# ul-12.net
KiCad netlist of a schematic drawn in EAGLE
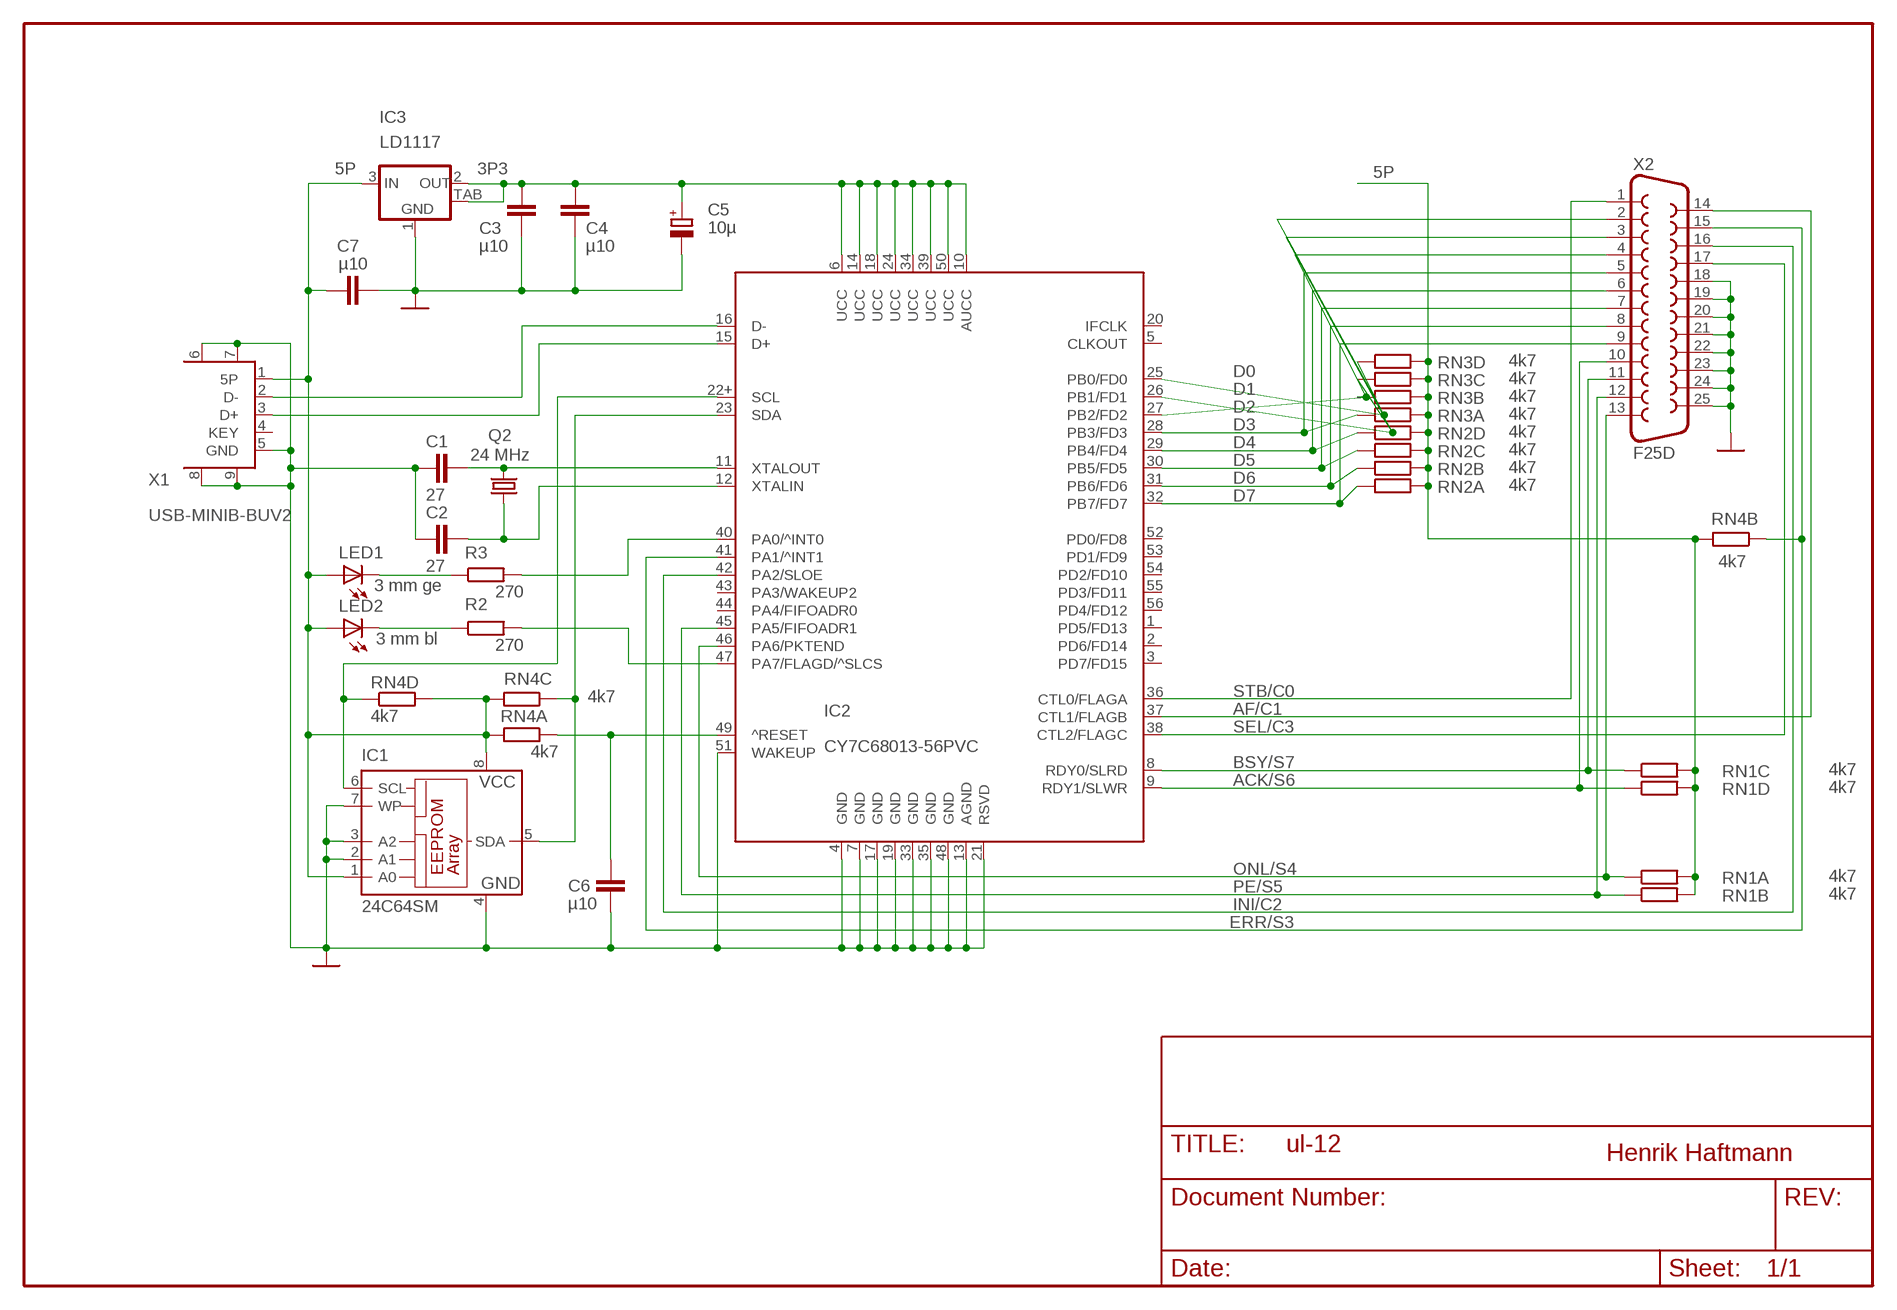
[diagram p0: schematic, sheet 1, part 1 of 2]
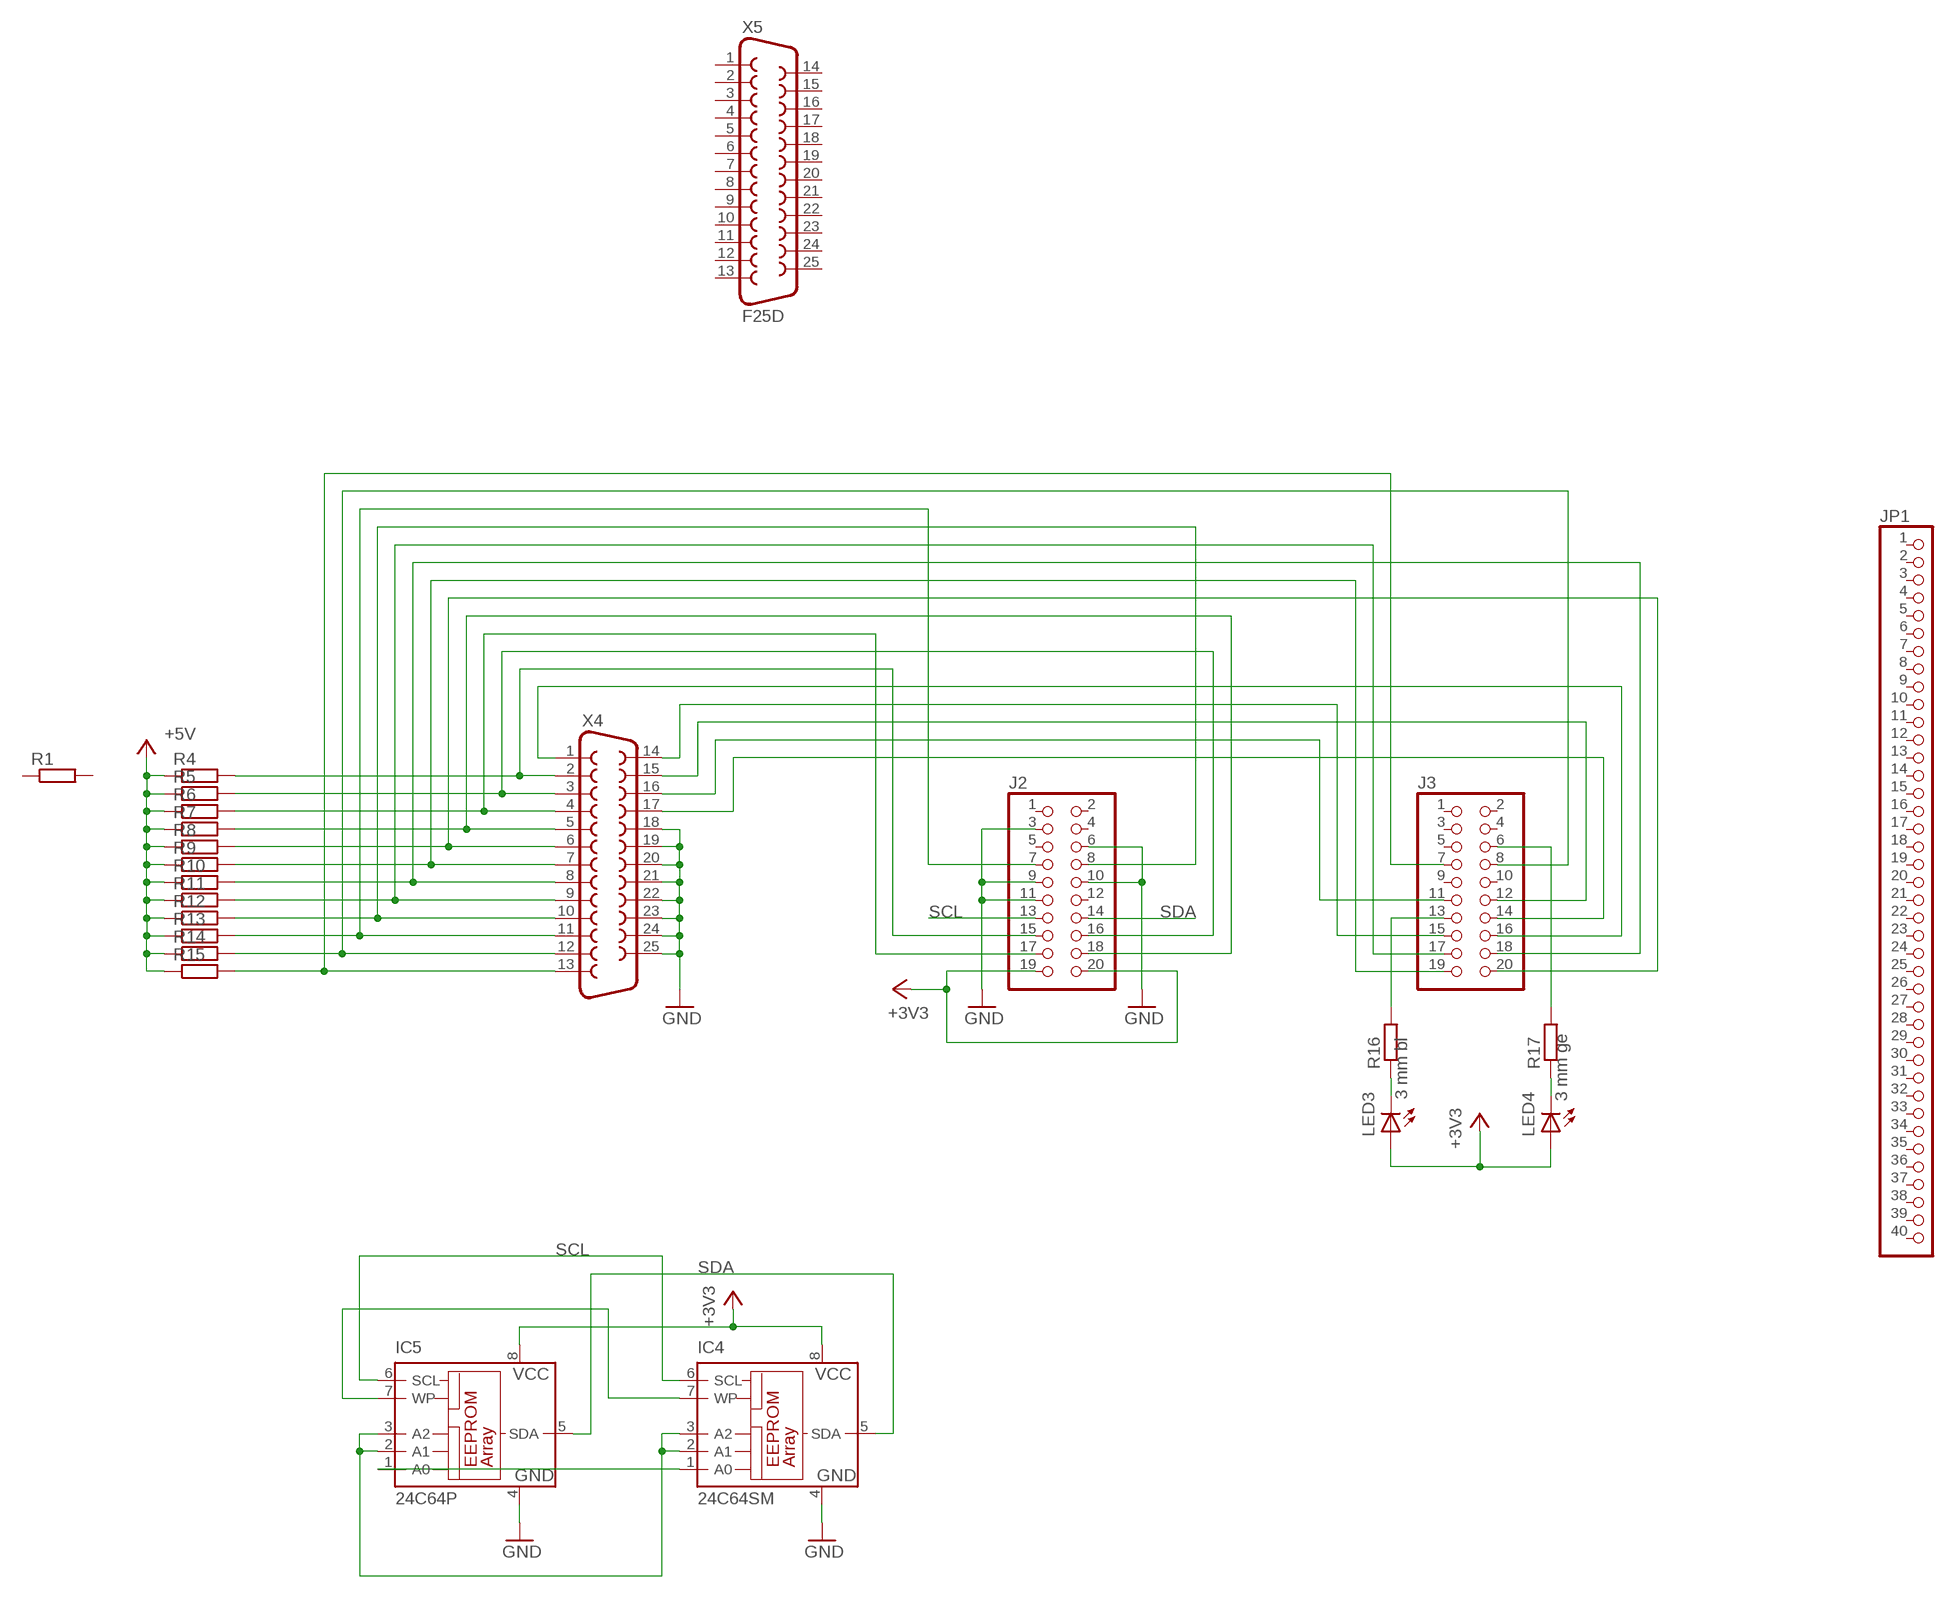
[diagram p1: schematic, sheet 1, part 2 of 2]

(export (version "E")
  (design (tool "Eeschema 10.0.6"))
  (components
    (comp (ref "C1")
      (value "27")
      (footprint "eagle-import:C0805")
      (libsource (lib "eagle-import") (part "C-EUC0805"))
    )
    (comp (ref "C2")
      (value "27")
      (footprint "eagle-import:C0805")
      (libsource (lib "eagle-import") (part "C-EUC0805"))
    )
    (comp (ref "C3")
      (value "µ10")
      (footprint "eagle-import:C0805")
      (libsource (lib "eagle-import") (part "C-EUC0805"))
    )
    (comp (ref "C4")
      (value "µ10")
      (footprint "eagle-import:C0805")
      (libsource (lib "eagle-import") (part "C-EUC0805"))
    )
    (comp (ref "C5")
      (value "10µ")
      (footprint "eagle-import:C_6032-28R")
      (libsource (lib "eagle-import") (part "CPOL-EUC/6032-28R"))
    )
    (comp (ref "C6")
      (value "µ10")
      (footprint "eagle-import:C0805")
      (libsource (lib "eagle-import") (part "C-EUC0805"))
    )
    (comp (ref "C7")
      (value "µ10")
      (footprint "eagle-import:C0805")
      (libsource (lib "eagle-import") (part "C-EUC0805"))
    )
    (comp (ref "IC1")
      (value "24C64SM")
      (footprint "eagle-import:SO-08M")
      (libsource (lib "eagle-import") (part "24SMC64"))
    )
    (comp (ref "IC2")
      (value "CY7C68013-56PVC")
      (footprint "eagle-import:SSOP56")
      (libsource (lib "eagle-import") (part "CY7C68013-56PVC"))
    )
    (comp (ref "IC3")
      (value "LD1117")
      (footprint "eagle-import:SOT223")
      (libsource (lib "eagle-import") (part "LD1117S"))
    )
    (comp (ref "IC4")
      (value "24C64SM")
      (footprint "eagle-import:SO-08M")
      (libsource (lib "eagle-import") (part "24SMC64"))
    )
    (comp (ref "IC5")
      (value "24C64P")
      (footprint "eagle-import:DIL8")
      (libsource (lib "eagle-import") (part "24PC64"))
    )
    (comp (ref "J2")
      (value "PINHD-2X10")
      (footprint "eagle-import:2X10")
      (libsource (lib "eagle-import") (part "PINHD-2X10"))
    )
    (comp (ref "J3")
      (value "PINHD-2X10")
      (footprint "eagle-import:2X10")
      (libsource (lib "eagle-import") (part "PINHD-2X10"))
    )
    (comp (ref "JP1")
      (value "PINHD-1X40")
      (footprint "eagle-import:1X40")
      (libsource (lib "eagle-import") (part "PINHD-1X40"))
    )
    (comp (ref "LED1")
      (value "3 mm ge")
      (footprint "eagle-import:LED3MM")
      (libsource (lib "eagle-import") (part "LED3MM"))
    )
    (comp (ref "LED2")
      (value "3 mm bl")
      (footprint "eagle-import:LED3MM")
      (libsource (lib "eagle-import") (part "LED3MM"))
    )
    (comp (ref "LED3")
      (value "3 mm bl")
      (footprint "eagle-import:LED3MM")
      (libsource (lib "eagle-import") (part "LED3MM"))
    )
    (comp (ref "LED4")
      (value "3 mm ge")
      (footprint "eagle-import:LED3MM")
      (libsource (lib "eagle-import") (part "LED3MM"))
    )
    (comp (ref "Q2")
      (value "24 MHz")
      (footprint "eagle-import:HC49U-V")
      (libsource (lib "eagle-import") (part "CRYTALHC49U-V"))
    )
    (comp (ref "R1")
      (value "R-EU_R0805")
      (footprint "eagle-import:R0805")
      (libsource (lib "eagle-import") (part "R-EU_R0805"))
    )
    (comp (ref "R2")
      (value "270")
      (footprint "eagle-import:R0805")
      (libsource (lib "eagle-import") (part "R-EU_R0805"))
    )
    (comp (ref "R3")
      (value "270")
      (footprint "eagle-import:R0805")
      (libsource (lib "eagle-import") (part "R-EU_R0805"))
    )
    (comp (ref "R4")
      (value "R-EU_R0805")
      (footprint "eagle-import:R0805")
      (libsource (lib "eagle-import") (part "R-EU_R0805"))
    )
    (comp (ref "R5")
      (value "R-EU_R0805")
      (footprint "eagle-import:R0805")
      (libsource (lib "eagle-import") (part "R-EU_R0805"))
    )
    (comp (ref "R6")
      (value "R-EU_R0805")
      (footprint "eagle-import:R0805")
      (libsource (lib "eagle-import") (part "R-EU_R0805"))
    )
    (comp (ref "R7")
      (value "R-EU_R0805")
      (footprint "eagle-import:R0805")
      (libsource (lib "eagle-import") (part "R-EU_R0805"))
    )
    (comp (ref "R8")
      (value "R-EU_R0805")
      (footprint "eagle-import:R0805")
      (libsource (lib "eagle-import") (part "R-EU_R0805"))
    )
    (comp (ref "R9")
      (value "R-EU_R0805")
      (footprint "eagle-import:R0805")
      (libsource (lib "eagle-import") (part "R-EU_R0805"))
    )
    (comp (ref "R10")
      (value "R-EU_R0805")
      (footprint "eagle-import:R0805")
      (libsource (lib "eagle-import") (part "R-EU_R0805"))
    )
    (comp (ref "R11")
      (value "R-EU_R0805")
      (footprint "eagle-import:R0805")
      (libsource (lib "eagle-import") (part "R-EU_R0805"))
    )
    (comp (ref "R12")
      (value "R-EU_R0805")
      (footprint "eagle-import:R0805")
      (libsource (lib "eagle-import") (part "R-EU_R0805"))
    )
    (comp (ref "R13")
      (value "R-EU_R0805")
      (footprint "eagle-import:R0805")
      (libsource (lib "eagle-import") (part "R-EU_R0805"))
    )
    (comp (ref "R14")
      (value "R-EU_R0805")
      (footprint "eagle-import:R0805")
      (libsource (lib "eagle-import") (part "R-EU_R0805"))
    )
    (comp (ref "R15")
      (value "R-EU_R0805")
      (footprint "eagle-import:R0805")
      (libsource (lib "eagle-import") (part "R-EU_R0805"))
    )
    (comp (ref "R16")
      (value "R-EU_R0805")
      (footprint "eagle-import:R0805")
      (libsource (lib "eagle-import") (part "R-EU_R0805"))
    )
    (comp (ref "R17")
      (value "R-EU_R0805")
      (footprint "eagle-import:R0805")
      (libsource (lib "eagle-import") (part "R-EU_R0805"))
    )
    (comp (ref "RN1")
      (value "4k7")
      (footprint "eagle-import:R-4P")
      (libsource (lib "eagle-import") (part "RN-4P1206"))
    )
    (comp (ref "RN2")
      (value "4k7")
      (footprint "eagle-import:R-4P")
      (libsource (lib "eagle-import") (part "RN-4P1206"))
    )
    (comp (ref "RN3")
      (value "4k7")
      (footprint "eagle-import:R-4P")
      (libsource (lib "eagle-import") (part "RN-4P1206"))
    )
    (comp (ref "RN4")
      (value "4k7")
      (footprint "eagle-import:R-4P")
      (libsource (lib "eagle-import") (part "RN-4P1206"))
    )
    (comp (ref "X1")
      (value "USB-MINIB-BUV2")
      (footprint "eagle-import:USB-MINIB-BUO")
      (libsource (lib "eagle-import") (part "USB-MINIB-BUV2"))
    )
    (comp (ref "X2")
      (value "F25D")
      (footprint "eagle-import:F25D")
      (libsource (lib "eagle-import") (part "hs-ul_F25D"))
    )
    (comp (ref "X4")
      (value "F25HP")
      (footprint "eagle-import:F25HP")
      (libsource (lib "eagle-import") (part "F25HP"))
    )
    (comp (ref "X5")
      (value "F25D")
      (footprint "eagle-import:F25D")
      (libsource (lib "eagle-import") (part "hs-ul_F25D"))
    )
  )
  (nets
    (net (code "1") (name "+3V3") (class "Default")
      (node (ref "IC4") (pin "8") (pinfunction "VCC_8") (pintype "power_in"))
      (node (ref "IC5") (pin "8") (pinfunction "VCC_8") (pintype "power_in"))
      (node (ref "J2") (pin "19") (pinfunction "19_19") (pintype "passive"))
      (node (ref "J2") (pin "20") (pinfunction "20_20") (pintype "passive"))
      (node (ref "LED3") (pin "A") (pinfunction "A_A") (pintype "passive"))
      (node (ref "LED4") (pin "A") (pinfunction "A_A") (pintype "passive"))
    )
    (net (code "2") (name "+5V") (class "Default")
      (node (ref "R10") (pin "1") (pinfunction "1_1") (pintype "passive"))
      (node (ref "R11") (pin "1") (pinfunction "1_1") (pintype "passive"))
      (node (ref "R12") (pin "1") (pinfunction "1_1") (pintype "passive"))
      (node (ref "R13") (pin "1") (pinfunction "1_1") (pintype "passive"))
      (node (ref "R14") (pin "1") (pinfunction "1_1") (pintype "passive"))
      (node (ref "R15") (pin "1") (pinfunction "1_1") (pintype "passive"))
      (node (ref "R4") (pin "1") (pinfunction "1_1") (pintype "passive"))
      (node (ref "R5") (pin "1") (pinfunction "1_1") (pintype "passive"))
      (node (ref "R6") (pin "1") (pinfunction "1_1") (pintype "passive"))
      (node (ref "R7") (pin "1") (pinfunction "1_1") (pintype "passive"))
      (node (ref "R8") (pin "1") (pinfunction "1_1") (pintype "passive"))
      (node (ref "R9") (pin "1") (pinfunction "1_1") (pintype "passive"))
    )
    (net (code "3") (name "/3P3") (class "Default")
      (node (ref "C3") (pin "2") (pinfunction "2_2") (pintype "passive"))
      (node (ref "C4") (pin "2") (pinfunction "2_2") (pintype "passive"))
      (node (ref "C5") (pin "+") (pinfunction "+_+") (pintype "passive"))
      (node (ref "IC2") (pin "10") (pinfunction "AUCC_10") (pintype "power_in"))
      (node (ref "IC2") (pin "14") (pinfunction "UCC_14") (pintype "power_in"))
      (node (ref "IC2") (pin "18") (pinfunction "UCC_18") (pintype "power_in"))
      (node (ref "IC2") (pin "24") (pinfunction "UCC_24") (pintype "power_in"))
      (node (ref "IC2") (pin "34") (pinfunction "UCC_34") (pintype "power_in"))
      (node (ref "IC2") (pin "39") (pinfunction "UCC_39") (pintype "power_in"))
      (node (ref "IC2") (pin "50") (pinfunction "UCC_50") (pintype "power_in"))
      (node (ref "IC2") (pin "6") (pinfunction "UCC_6") (pintype "power_in"))
      (node (ref "IC3") (pin "2") (pinfunction "OUT_2") (pintype "passive"))
      (node (ref "IC3") (pin "TAB") (pinfunction "OUT_TAB") (pintype "passive"))
    )
    (net (code "4") (name "/5P") (class "Default")
      (node (ref "C7") (pin "2") (pinfunction "2_2") (pintype "passive"))
      (node (ref "IC1") (pin "1") (pinfunction "A0_1") (pintype "input"))
      (node (ref "IC1") (pin "8") (pinfunction "VCC_8") (pintype "power_in"))
      (node (ref "IC3") (pin "3") (pinfunction "IN_3") (pintype "input"))
      (node (ref "LED1") (pin "A") (pinfunction "A_A") (pintype "passive"))
      (node (ref "LED2") (pin "A") (pinfunction "A_A") (pintype "passive"))
      (node (ref "RN1") (pin "5") (pinfunction "2_5") (pintype "passive"))
      (node (ref "RN1") (pin "6") (pinfunction "2_6") (pintype "passive"))
      (node (ref "RN1") (pin "7") (pinfunction "2_7") (pintype "passive"))
      (node (ref "RN1") (pin "8") (pinfunction "2_8") (pintype "passive"))
      (node (ref "RN2") (pin "5") (pinfunction "2_5") (pintype "passive"))
      (node (ref "RN2") (pin "6") (pinfunction "2_6") (pintype "passive"))
      (node (ref "RN2") (pin "7") (pinfunction "2_7") (pintype "passive"))
      (node (ref "RN2") (pin "8") (pinfunction "2_8") (pintype "passive"))
      (node (ref "RN3") (pin "5") (pinfunction "2_5") (pintype "passive"))
      (node (ref "RN3") (pin "6") (pinfunction "2_6") (pintype "passive"))
      (node (ref "RN3") (pin "7") (pinfunction "2_7") (pintype "passive"))
      (node (ref "RN3") (pin "8") (pinfunction "2_8") (pintype "passive"))
      (node (ref "RN4") (pin "5") (pinfunction "2_5") (pintype "passive"))
      (node (ref "RN4") (pin "6") (pinfunction "2_6") (pintype "passive"))
      (node (ref "RN4") (pin "7") (pinfunction "2_7") (pintype "passive"))
      (node (ref "RN4") (pin "8") (pinfunction "2_8") (pintype "passive"))
      (node (ref "X1") (pin "1") (pinfunction "5P_1") (pintype "power_in"))
    )
    (net (code "5") (name "/ACK{slash}S6") (class "Default")
      (node (ref "IC2") (pin "9") (pinfunction "RDY1/SLWR_9") (pintype "input"))
      (node (ref "RN1") (pin "4") (pinfunction "1_4") (pintype "passive"))
      (node (ref "X2") (pin "10") (pinfunction "10_10") (pintype "passive"))
    )
    (net (code "6") (name "/AF{slash}C1") (class "Default")
      (node (ref "IC2") (pin "37") (pinfunction "CTL1/FLAGB_37") (pintype "tri_state"))
      (node (ref "X2") (pin "14") (pinfunction "14_14") (pintype "passive"))
    )
    (net (code "7") (name "/BSY{slash}S7") (class "Default")
      (node (ref "IC2") (pin "8") (pinfunction "RDY0/SLRD_8") (pintype "input"))
      (node (ref "RN1") (pin "3") (pinfunction "1_3") (pintype "passive"))
      (node (ref "X2") (pin "11") (pinfunction "11_11") (pintype "passive"))
    )
    (net (code "8") (name "/D0") (class "Default")
      (node (ref "IC2") (pin "25") (pinfunction "PB0/FD0_25") (pintype "bidirectional"))
      (node (ref "RN3") (pin "4") (pinfunction "1_4") (pintype "passive"))
      (node (ref "X2") (pin "2") (pinfunction "2_2") (pintype "passive"))
    )
    (net (code "9") (name "/D1") (class "Default")
      (node (ref "IC2") (pin "26") (pinfunction "PB1/FD1_26") (pintype "bidirectional"))
      (node (ref "RN3") (pin "3") (pinfunction "1_3") (pintype "passive"))
      (node (ref "X2") (pin "3") (pinfunction "3_3") (pintype "passive"))
    )
    (net (code "10") (name "/D2") (class "Default")
      (node (ref "IC2") (pin "27") (pinfunction "PB2/FD2_27") (pintype "bidirectional"))
      (node (ref "RN3") (pin "2") (pinfunction "1_2") (pintype "passive"))
      (node (ref "X2") (pin "4") (pinfunction "4_4") (pintype "passive"))
    )
    (net (code "11") (name "/D3") (class "Default")
      (node (ref "IC2") (pin "28") (pinfunction "PB3/FD3_28") (pintype "bidirectional"))
      (node (ref "RN3") (pin "1") (pinfunction "1_1") (pintype "passive"))
      (node (ref "X2") (pin "5") (pinfunction "5_5") (pintype "passive"))
    )
    (net (code "12") (name "/D4") (class "Default")
      (node (ref "IC2") (pin "29") (pinfunction "PB4/FD4_29") (pintype "bidirectional"))
      (node (ref "RN2") (pin "4") (pinfunction "1_4") (pintype "passive"))
      (node (ref "X2") (pin "6") (pinfunction "6_6") (pintype "passive"))
    )
    (net (code "13") (name "/D5") (class "Default")
      (node (ref "IC2") (pin "30") (pinfunction "PB5/FD5_30") (pintype "bidirectional"))
      (node (ref "RN2") (pin "3") (pinfunction "1_3") (pintype "passive"))
      (node (ref "X2") (pin "7") (pinfunction "7_7") (pintype "passive"))
    )
    (net (code "14") (name "/D6") (class "Default")
      (node (ref "IC2") (pin "31") (pinfunction "PB6/FD6_31") (pintype "bidirectional"))
      (node (ref "RN2") (pin "2") (pinfunction "1_2") (pintype "passive"))
      (node (ref "X2") (pin "8") (pinfunction "8_8") (pintype "passive"))
    )
    (net (code "15") (name "/D7") (class "Default")
      (node (ref "IC2") (pin "32") (pinfunction "PB7/FD7_32") (pintype "bidirectional"))
      (node (ref "RN2") (pin "1") (pinfunction "1_1") (pintype "passive"))
      (node (ref "X2") (pin "9") (pinfunction "9_9") (pintype "passive"))
    )
    (net (code "16") (name "/ERR{slash}S3") (class "Default")
      (node (ref "IC2") (pin "41") (pinfunction "PA1/^INT1_41") (pintype "bidirectional"))
      (node (ref "RN4") (pin "2") (pinfunction "1_2") (pintype "passive"))
      (node (ref "X2") (pin "15") (pinfunction "15_15") (pintype "passive"))
    )
    (net (code "17") (name "/INI{slash}C2") (class "Default")
      (node (ref "IC2") (pin "42") (pinfunction "PA2/SLOE_42") (pintype "bidirectional"))
      (node (ref "X2") (pin "16") (pinfunction "16_16") (pintype "passive"))
    )
    (net (code "18") (name "/ONL{slash}S4") (class "Default")
      (node (ref "IC2") (pin "46") (pinfunction "PA6/PKTEND_46") (pintype "bidirectional"))
      (node (ref "RN1") (pin "1") (pinfunction "1_1") (pintype "passive"))
      (node (ref "X2") (pin "13") (pinfunction "13_13") (pintype "passive"))
    )
    (net (code "19") (name "/PE{slash}S5") (class "Default")
      (node (ref "IC2") (pin "45") (pinfunction "PA5/FIFOADR1_45") (pintype "bidirectional"))
      (node (ref "RN1") (pin "2") (pinfunction "1_2") (pintype "passive"))
      (node (ref "X2") (pin "12") (pinfunction "12_12") (pintype "passive"))
    )
    (net (code "20") (name "/SCL") (class "Default")
      (node (ref "IC4") (pin "6") (pinfunction "SCL_6") (pintype "input"))
      (node (ref "IC5") (pin "6") (pinfunction "SCL_6") (pintype "input"))
      (node (ref "J2") (pin "13") (pinfunction "13_13") (pintype "passive"))
    )
    (net (code "21") (name "/SDA") (class "Default")
      (node (ref "IC4") (pin "5") (pinfunction "SDA_5") (pintype "bidirectional"))
      (node (ref "IC5") (pin "5") (pinfunction "SDA_5") (pintype "bidirectional"))
      (node (ref "J2") (pin "14") (pinfunction "14_14") (pintype "passive"))
    )
    (net (code "22") (name "/SEL{slash}C3") (class "Default")
      (node (ref "IC2") (pin "38") (pinfunction "CTL2/FLAGC_38") (pintype "tri_state"))
      (node (ref "X2") (pin "17") (pinfunction "17_17") (pintype "passive"))
    )
    (net (code "23") (name "/STB{slash}C0") (class "Default")
      (node (ref "IC2") (pin "36") (pinfunction "CTL0/FLAGA_36") (pintype "tri_state"))
      (node (ref "X2") (pin "1") (pinfunction "1_1") (pintype "passive"))
    )
    (net (code "24") (name "GND") (class "Default")
      (node (ref "C1") (pin "2") (pinfunction "2_2") (pintype "passive"))
      (node (ref "C2") (pin "2") (pinfunction "2_2") (pintype "passive"))
      (node (ref "C3") (pin "1") (pinfunction "1_1") (pintype "passive"))
      (node (ref "C4") (pin "1") (pinfunction "1_1") (pintype "passive"))
      (node (ref "C5") (pin "-") (pinfunction "-_-") (pintype "passive"))
      (node (ref "C6") (pin "1") (pinfunction "1_1") (pintype "passive"))
      (node (ref "C7") (pin "1") (pinfunction "1_1") (pintype "passive"))
      (node (ref "IC1") (pin "2") (pinfunction "A1_2") (pintype "input"))
      (node (ref "IC1") (pin "3") (pinfunction "A2_3") (pintype "input"))
      (node (ref "IC1") (pin "4") (pinfunction "GND_4") (pintype "power_in"))
      (node (ref "IC1") (pin "7") (pinfunction "WP_7") (pintype "input"))
      (node (ref "IC2") (pin "13") (pinfunction "AGND_13") (pintype "power_in"))
      (node (ref "IC2") (pin "17") (pinfunction "GND_17") (pintype "power_in"))
      (node (ref "IC2") (pin "19") (pinfunction "GND_19") (pintype "power_in"))
      (node (ref "IC2") (pin "21") (pinfunction "RSVD_21") (pintype "input"))
      (node (ref "IC2") (pin "33") (pinfunction "GND_33") (pintype "power_in"))
      (node (ref "IC2") (pin "35") (pinfunction "GND_35") (pintype "power_in"))
      (node (ref "IC2") (pin "4") (pinfunction "GND_4") (pintype "power_in"))
      (node (ref "IC2") (pin "48") (pinfunction "GND_48") (pintype "power_in"))
      (node (ref "IC2") (pin "51") (pinfunction "WAKEUP_51") (pintype "input"))
      (node (ref "IC2") (pin "7") (pinfunction "GND_7") (pintype "power_in"))
      (node (ref "IC3") (pin "1") (pinfunction "GND_1") (pintype "power_in"))
      (node (ref "IC4") (pin "4") (pinfunction "GND_4") (pintype "power_in"))
      (node (ref "IC5") (pin "4") (pinfunction "GND_4") (pintype "power_in"))
      (node (ref "J2") (pin "10") (pinfunction "10_10") (pintype "passive"))
      (node (ref "J2") (pin "11") (pinfunction "11_11") (pintype "passive"))
      (node (ref "J2") (pin "3") (pinfunction "3_3") (pintype "passive"))
      (node (ref "J2") (pin "6") (pinfunction "6_6") (pintype "passive"))
      (node (ref "J2") (pin "9") (pinfunction "9_9") (pintype "passive"))
      (node (ref "X1") (pin "5") (pinfunction "GND_5") (pintype "power_in"))
      (node (ref "X1") (pin "6") (pinfunction "GND_6") (pintype "power_in"))
      (node (ref "X1") (pin "7") (pinfunction "GND_7") (pintype "power_in"))
      (node (ref "X1") (pin "8") (pinfunction "GND_8") (pintype "power_in"))
      (node (ref "X1") (pin "9") (pinfunction "GND_9") (pintype "power_in"))
      (node (ref "X2") (pin "18") (pinfunction "18_18") (pintype "passive"))
      (node (ref "X2") (pin "19") (pinfunction "19_19") (pintype "passive"))
      (node (ref "X2") (pin "20") (pinfunction "20_20") (pintype "passive"))
      (node (ref "X2") (pin "21") (pinfunction "21_21") (pintype "passive"))
      (node (ref "X2") (pin "22") (pinfunction "22_22") (pintype "passive"))
      (node (ref "X2") (pin "23") (pinfunction "23_23") (pintype "passive"))
      (node (ref "X2") (pin "24") (pinfunction "24_24") (pintype "passive"))
      (node (ref "X2") (pin "25") (pinfunction "25_25") (pintype "passive"))
      (node (ref "X4") (pin "18") (pinfunction "18_18") (pintype "passive"))
      (node (ref "X4") (pin "19") (pinfunction "19_19") (pintype "passive"))
      (node (ref "X4") (pin "20") (pinfunction "20_20") (pintype "passive"))
      (node (ref "X4") (pin "21") (pinfunction "21_21") (pintype "passive"))
      (node (ref "X4") (pin "22") (pinfunction "22_22") (pintype "passive"))
      (node (ref "X4") (pin "23") (pinfunction "23_23") (pintype "passive"))
      (node (ref "X4") (pin "24") (pinfunction "24_24") (pintype "passive"))
      (node (ref "X4") (pin "25") (pinfunction "25_25") (pintype "passive"))
    )
    (net (code "25") (name "Net-(IC1-SCL)") (class "Default")
      (node (ref "IC1") (pin "6") (pinfunction "SCL_6") (pintype "input"))
      (node (ref "IC2") (pin "22+") (pinfunction "SCL_22+") (pintype "open_collector"))
      (node (ref "RN4") (pin "4") (pinfunction "1_4") (pintype "passive"))
    )
    (net (code "26") (name "Net-(IC1-SDA)") (class "Default")
      (node (ref "IC1") (pin "5") (pinfunction "SDA_5") (pintype "bidirectional"))
      (node (ref "IC2") (pin "23") (pinfunction "SDA_23") (pintype "open_collector"))
      (node (ref "RN4") (pin "3") (pinfunction "1_3") (pintype "passive"))
    )
    (net (code "27") (name "Net-(IC2-D+)") (class "Default")
      (node (ref "IC2") (pin "15") (pinfunction "D+_15") (pintype "bidirectional"))
      (node (ref "X1") (pin "3") (pinfunction "D+_3") (pintype "bidirectional"))
    )
    (net (code "28") (name "Net-(IC2-D-)") (class "Default")
      (node (ref "IC2") (pin "16") (pinfunction "D-_16") (pintype "bidirectional"))
      (node (ref "X1") (pin "2") (pinfunction "D-_2") (pintype "bidirectional"))
    )
    (net (code "29") (name "Net-(IC2-PA0{slash}^INT0)") (class "Default")
      (node (ref "IC2") (pin "40") (pinfunction "PA0/^INT0_40") (pintype "bidirectional"))
      (node (ref "R3") (pin "2") (pinfunction "2_2") (pintype "passive"))
    )
    (net (code "30") (name "Net-(IC2-PA7{slash}FLAGD{slash}^SLCS)") (class "Default")
      (node (ref "IC2") (pin "47") (pinfunction "PA7/FLAGD/^SLCS_47") (pintype "bidirectional"))
      (node (ref "R2") (pin "2") (pinfunction "2_2") (pintype "passive"))
    )
    (net (code "31") (name "Net-(IC2-XTALIN)") (class "Default")
      (node (ref "C2") (pin "1") (pinfunction "1_1") (pintype "passive"))
      (node (ref "IC2") (pin "12") (pinfunction "XTALIN_12") (pintype "input"))
      (node (ref "Q2") (pin "1") (pinfunction "1_1") (pintype "passive"))
    )
    (net (code "32") (name "Net-(IC2-XTALOUT)") (class "Default")
      (node (ref "C1") (pin "1") (pinfunction "1_1") (pintype "passive"))
      (node (ref "IC2") (pin "11") (pinfunction "XTALOUT_11") (pintype "output"))
      (node (ref "Q2") (pin "2") (pinfunction "2_2") (pintype "passive"))
    )
    (net (code "33") (name "Net-(IC2-^RESET)") (class "Default")
      (node (ref "C6") (pin "2") (pinfunction "2_2") (pintype "passive"))
      (node (ref "IC2") (pin "49") (pinfunction "^RESET_49") (pintype "input"))
      (node (ref "RN4") (pin "1") (pinfunction "1_1") (pintype "passive"))
    )
    (net (code "34") (name "Net-(IC4-A0)") (class "Default")
      (node (ref "IC4") (pin "1") (pinfunction "A0_1") (pintype "input"))
      (node (ref "IC5") (pin "1") (pinfunction "A0_1") (pintype "input"))
    )
    (net (code "35") (name "Net-(IC4-A1)") (class "Default")
      (node (ref "IC4") (pin "2") (pinfunction "A1_2") (pintype "input"))
      (node (ref "IC4") (pin "3") (pinfunction "A2_3") (pintype "input"))
      (node (ref "IC5") (pin "2") (pinfunction "A1_2") (pintype "input"))
      (node (ref "IC5") (pin "3") (pinfunction "A2_3") (pintype "input"))
    )
    (net (code "36") (name "Net-(IC4-WP)") (class "Default")
      (node (ref "IC4") (pin "7") (pinfunction "WP_7") (pintype "input"))
      (node (ref "IC5") (pin "7") (pinfunction "WP_7") (pintype "input"))
    )
    (net (code "37") (name "Net-(J2-Pad7)") (class "Default")
      (node (ref "J2") (pin "7") (pinfunction "7_7") (pintype "passive"))
      (node (ref "R13") (pin "2") (pinfunction "2_2") (pintype "passive"))
      (node (ref "X4") (pin "11") (pinfunction "11_11") (pintype "passive"))
    )
    (net (code "38") (name "Net-(J2-Pad8)") (class "Default")
      (node (ref "J2") (pin "8") (pinfunction "8_8") (pintype "passive"))
      (node (ref "R12") (pin "2") (pinfunction "2_2") (pintype "passive"))
      (node (ref "X4") (pin "10") (pinfunction "10_10") (pintype "passive"))
    )
    (net (code "39") (name "Net-(J2-Pad15)") (class "Default")
      (node (ref "J2") (pin "15") (pinfunction "15_15") (pintype "passive"))
      (node (ref "R4") (pin "2") (pinfunction "2_2") (pintype "passive"))
      (node (ref "X4") (pin "2") (pinfunction "2_2") (pintype "passive"))
    )
    (net (code "40") (name "Net-(J2-Pad16)") (class "Default")
      (node (ref "J2") (pin "16") (pinfunction "16_16") (pintype "passive"))
      (node (ref "R5") (pin "2") (pinfunction "2_2") (pintype "passive"))
      (node (ref "X4") (pin "3") (pinfunction "3_3") (pintype "passive"))
    )
    (net (code "41") (name "Net-(J2-Pad17)") (class "Default")
      (node (ref "J2") (pin "17") (pinfunction "17_17") (pintype "passive"))
      (node (ref "R6") (pin "2") (pinfunction "2_2") (pintype "passive"))
      (node (ref "X4") (pin "4") (pinfunction "4_4") (pintype "passive"))
    )
    (net (code "42") (name "Net-(J2-Pad18)") (class "Default")
      (node (ref "J2") (pin "18") (pinfunction "18_18") (pintype "passive"))
      (node (ref "R7") (pin "2") (pinfunction "2_2") (pintype "passive"))
      (node (ref "X4") (pin "5") (pinfunction "5_5") (pintype "passive"))
    )
    (net (code "43") (name "Net-(J3-Pad6)") (class "Default")
      (node (ref "J3") (pin "6") (pinfunction "6_6") (pintype "passive"))
      (node (ref "R17") (pin "2") (pinfunction "2_2") (pintype "passive"))
    )
    (net (code "44") (name "Net-(J3-Pad7)") (class "Default")
      (node (ref "J3") (pin "7") (pinfunction "7_7") (pintype "passive"))
      (node (ref "R15") (pin "2") (pinfunction "2_2") (pintype "passive"))
      (node (ref "X4") (pin "13") (pinfunction "13_13") (pintype "passive"))
    )
    (net (code "45") (name "Net-(J3-Pad8)") (class "Default")
      (node (ref "J3") (pin "8") (pinfunction "8_8") (pintype "passive"))
      (node (ref "R14") (pin "2") (pinfunction "2_2") (pintype "passive"))
      (node (ref "X4") (pin "12") (pinfunction "12_12") (pintype "passive"))
    )
    (net (code "46") (name "Net-(J3-Pad11)") (class "Default")
      (node (ref "J3") (pin "11") (pinfunction "11_11") (pintype "passive"))
      (node (ref "X4") (pin "16") (pinfunction "16_16") (pintype "passive"))
    )
    (net (code "47") (name "Net-(J3-Pad12)") (class "Default")
      (node (ref "J3") (pin "12") (pinfunction "12_12") (pintype "passive"))
      (node (ref "X4") (pin "15") (pinfunction "15_15") (pintype "passive"))
    )
    (net (code "48") (name "Net-(J3-Pad13)") (class "Default")
      (node (ref "J3") (pin "13") (pinfunction "13_13") (pintype "passive"))
      (node (ref "R16") (pin "2") (pinfunction "2_2") (pintype "passive"))
    )
    (net (code "49") (name "Net-(J3-Pad14)") (class "Default")
      (node (ref "J3") (pin "14") (pinfunction "14_14") (pintype "passive"))
      (node (ref "X4") (pin "17") (pinfunction "17_17") (pintype "passive"))
    )
    (net (code "50") (name "Net-(J3-Pad15)") (class "Default")
      (node (ref "J3") (pin "15") (pinfunction "15_15") (pintype "passive"))
      (node (ref "X4") (pin "14") (pinfunction "14_14") (pintype "passive"))
    )
    (net (code "51") (name "Net-(J3-Pad16)") (class "Default")
      (node (ref "J3") (pin "16") (pinfunction "16_16") (pintype "passive"))
      (node (ref "X4") (pin "1") (pinfunction "1_1") (pintype "passive"))
    )
    (net (code "52") (name "Net-(J3-Pad17)") (class "Default")
      (node (ref "J3") (pin "17") (pinfunction "17_17") (pintype "passive"))
      (node (ref "R11") (pin "2") (pinfunction "2_2") (pintype "passive"))
      (node (ref "X4") (pin "9") (pinfunction "9_9") (pintype "passive"))
    )
    (net (code "53") (name "Net-(J3-Pad18)") (class "Default")
      (node (ref "J3") (pin "18") (pinfunction "18_18") (pintype "passive"))
      (node (ref "R10") (pin "2") (pinfunction "2_2") (pintype "passive"))
      (node (ref "X4") (pin "8") (pinfunction "8_8") (pintype "passive"))
    )
    (net (code "54") (name "Net-(J3-Pad19)") (class "Default")
      (node (ref "J3") (pin "19") (pinfunction "19_19") (pintype "passive"))
      (node (ref "R9") (pin "2") (pinfunction "2_2") (pintype "passive"))
      (node (ref "X4") (pin "7") (pinfunction "7_7") (pintype "passive"))
    )
    (net (code "55") (name "Net-(J3-Pad20)") (class "Default")
      (node (ref "J3") (pin "20") (pinfunction "20_20") (pintype "passive"))
      (node (ref "R8") (pin "2") (pinfunction "2_2") (pintype "passive"))
      (node (ref "X4") (pin "6") (pinfunction "6_6") (pintype "passive"))
    )
    (net (code "56") (name "Net-(LED1-C)") (class "Default")
      (node (ref "LED1") (pin "K") (pinfunction "C_K") (pintype "passive"))
      (node (ref "R3") (pin "1") (pinfunction "1_1") (pintype "passive"))
    )
    (net (code "57") (name "Net-(LED2-C)") (class "Default")
      (node (ref "LED2") (pin "K") (pinfunction "C_K") (pintype "passive"))
      (node (ref "R2") (pin "1") (pinfunction "1_1") (pintype "passive"))
    )
    (net (code "58") (name "Net-(LED3-C)") (class "Default")
      (node (ref "LED3") (pin "K") (pinfunction "C_K") (pintype "passive"))
      (node (ref "R16") (pin "1") (pinfunction "1_1") (pintype "passive"))
    )
    (net (code "59") (name "Net-(LED4-C)") (class "Default")
      (node (ref "LED4") (pin "K") (pinfunction "C_K") (pintype "passive"))
      (node (ref "R17") (pin "1") (pinfunction "1_1") (pintype "passive"))
    )
    (net (code "60") (name "unconnected-(IC2-CLKOUT-Pad5)") (class "Default")
      (node (ref "IC2") (pin "5") (pinfunction "CLKOUT_5") (pintype "tri_state"))
    )
    (net (code "61") (name "unconnected-(IC2-IFCLK-Pad20)") (class "Default")
      (node (ref "IC2") (pin "20") (pinfunction "IFCLK_20") (pintype "bidirectional"))
    )
    (net (code "62") (name "unconnected-(IC2-PA3{slash}WAKEUP2-Pad43)") (class "Default")
      (node (ref "IC2") (pin "43") (pinfunction "PA3/WAKEUP2_43") (pintype "bidirectional"))
    )
    (net (code "63") (name "unconnected-(IC2-PA4{slash}FIFOADR0-Pad44)") (class "Default")
      (node (ref "IC2") (pin "44") (pinfunction "PA4/FIFOADR0_44") (pintype "bidirectional"))
    )
    (net (code "64") (name "unconnected-(IC2-PD0{slash}FD8-Pad52)") (class "Default")
      (node (ref "IC2") (pin "52") (pinfunction "PD0/FD8_52") (pintype "bidirectional"))
    )
    (net (code "65") (name "unconnected-(IC2-PD1{slash}FD9-Pad53)") (class "Default")
      (node (ref "IC2") (pin "53") (pinfunction "PD1/FD9_53") (pintype "bidirectional"))
    )
    (net (code "66") (name "unconnected-(IC2-PD2{slash}FD10-Pad54)") (class "Default")
      (node (ref "IC2") (pin "54") (pinfunction "PD2/FD10_54") (pintype "bidirectional"))
    )
    (net (code "67") (name "unconnected-(IC2-PD3{slash}FD11-Pad55)") (class "Default")
      (node (ref "IC2") (pin "55") (pinfunction "PD3/FD11_55") (pintype "bidirectional"))
    )
    (net (code "68") (name "unconnected-(IC2-PD4{slash}FD12-Pad56)") (class "Default")
      (node (ref "IC2") (pin "56") (pinfunction "PD4/FD12_56") (pintype "bidirectional"))
    )
    (net (code "69") (name "unconnected-(IC2-PD5{slash}FD13-Pad1)") (class "Default")
      (node (ref "IC2") (pin "1") (pinfunction "PD5/FD13_1") (pintype "bidirectional"))
    )
    (net (code "70") (name "unconnected-(IC2-PD6{slash}FD14-Pad2)") (class "Default")
      (node (ref "IC2") (pin "2") (pinfunction "PD6/FD14_2") (pintype "bidirectional"))
    )
    (net (code "71") (name "unconnected-(IC2-PD7{slash}FD15-Pad3)") (class "Default")
      (node (ref "IC2") (pin "3") (pinfunction "PD7/FD15_3") (pintype "bidirectional"))
    )
    (net (code "72") (name "unconnected-(J2-Pad1)") (class "Default")
      (node (ref "J2") (pin "1") (pinfunction "1_1") (pintype "passive"))
    )
    (net (code "73") (name "unconnected-(J2-Pad2)") (class "Default")
      (node (ref "J2") (pin "2") (pinfunction "2_2") (pintype "passive"))
    )
    (net (code "74") (name "unconnected-(J2-Pad4)") (class "Default")
      (node (ref "J2") (pin "4") (pinfunction "4_4") (pintype "passive"))
    )
    (net (code "75") (name "unconnected-(J2-Pad5)") (class "Default")
      (node (ref "J2") (pin "5") (pinfunction "5_5") (pintype "passive"))
    )
    (net (code "76") (name "unconnected-(J2-Pad12)") (class "Default")
      (node (ref "J2") (pin "12") (pinfunction "12_12") (pintype "passive"))
    )
    (net (code "77") (name "unconnected-(J3-Pad1)") (class "Default")
      (node (ref "J3") (pin "1") (pinfunction "1_1") (pintype "passive"))
    )
    (net (code "78") (name "unconnected-(J3-Pad2)") (class "Default")
      (node (ref "J3") (pin "2") (pinfunction "2_2") (pintype "passive"))
    )
    (net (code "79") (name "unconnected-(J3-Pad3)") (class "Default")
      (node (ref "J3") (pin "3") (pinfunction "3_3") (pintype "passive"))
    )
    (net (code "80") (name "unconnected-(J3-Pad4)") (class "Default")
      (node (ref "J3") (pin "4") (pinfunction "4_4") (pintype "passive"))
    )
    (net (code "81") (name "unconnected-(J3-Pad5)") (class "Default")
      (node (ref "J3") (pin "5") (pinfunction "5_5") (pintype "passive"))
    )
    (net (code "82") (name "unconnected-(J3-Pad9)") (class "Default")
      (node (ref "J3") (pin "9") (pinfunction "9_9") (pintype "passive"))
    )
    (net (code "83") (name "unconnected-(J3-Pad10)") (class "Default")
      (node (ref "J3") (pin "10") (pinfunction "10_10") (pintype "passive"))
    )
    (net (code "84") (name "unconnected-(JP1-Pad1)") (class "Default")
      (node (ref "JP1") (pin "1") (pinfunction "1_1") (pintype "passive"))
    )
    (net (code "85") (name "unconnected-(JP1-Pad2)") (class "Default")
      (node (ref "JP1") (pin "2") (pinfunction "2_2") (pintype "passive"))
    )
    (net (code "86") (name "unconnected-(JP1-Pad3)") (class "Default")
      (node (ref "JP1") (pin "3") (pinfunction "3_3") (pintype "passive"))
    )
    (net (code "87") (name "unconnected-(JP1-Pad4)") (class "Default")
      (node (ref "JP1") (pin "4") (pinfunction "4_4") (pintype "passive"))
    )
    (net (code "88") (name "unconnected-(JP1-Pad5)") (class "Default")
      (node (ref "JP1") (pin "5") (pinfunction "5_5") (pintype "passive"))
    )
    (net (code "89") (name "unconnected-(JP1-Pad6)") (class "Default")
      (node (ref "JP1") (pin "6") (pinfunction "6_6") (pintype "passive"))
    )
    (net (code "90") (name "unconnected-(JP1-Pad7)") (class "Default")
      (node (ref "JP1") (pin "7") (pinfunction "7_7") (pintype "passive"))
    )
    (net (code "91") (name "unconnected-(JP1-Pad8)") (class "Default")
      (node (ref "JP1") (pin "8") (pinfunction "8_8") (pintype "passive"))
    )
    (net (code "92") (name "unconnected-(JP1-Pad9)") (class "Default")
      (node (ref "JP1") (pin "9") (pinfunction "9_9") (pintype "passive"))
    )
    (net (code "93") (name "unconnected-(JP1-Pad10)") (class "Default")
      (node (ref "JP1") (pin "10") (pinfunction "10_10") (pintype "passive"))
    )
    (net (code "94") (name "unconnected-(JP1-Pad11)") (class "Default")
      (node (ref "JP1") (pin "11") (pinfunction "11_11") (pintype "passive"))
    )
    (net (code "95") (name "unconnected-(JP1-Pad12)") (class "Default")
      (node (ref "JP1") (pin "12") (pinfunction "12_12") (pintype "passive"))
    )
    (net (code "96") (name "unconnected-(JP1-Pad13)") (class "Default")
      (node (ref "JP1") (pin "13") (pinfunction "13_13") (pintype "passive"))
    )
    (net (code "97") (name "unconnected-(JP1-Pad14)") (class "Default")
      (node (ref "JP1") (pin "14") (pinfunction "14_14") (pintype "passive"))
    )
    (net (code "98") (name "unconnected-(JP1-Pad15)") (class "Default")
      (node (ref "JP1") (pin "15") (pinfunction "15_15") (pintype "passive"))
    )
    (net (code "99") (name "unconnected-(JP1-Pad16)") (class "Default")
      (node (ref "JP1") (pin "16") (pinfunction "16_16") (pintype "passive"))
    )
    (net (code "100") (name "unconnected-(JP1-Pad17)") (class "Default")
      (node (ref "JP1") (pin "17") (pinfunction "17_17") (pintype "passive"))
    )
    (net (code "101") (name "unconnected-(JP1-Pad18)") (class "Default")
      (node (ref "JP1") (pin "18") (pinfunction "18_18") (pintype "passive"))
    )
    (net (code "102") (name "unconnected-(JP1-Pad19)") (class "Default")
      (node (ref "JP1") (pin "19") (pinfunction "19_19") (pintype "passive"))
    )
    (net (code "103") (name "unconnected-(JP1-Pad20)") (class "Default")
      (node (ref "JP1") (pin "20") (pinfunction "20_20") (pintype "passive"))
    )
    (net (code "104") (name "unconnected-(JP1-Pad21)") (class "Default")
      (node (ref "JP1") (pin "21") (pinfunction "21_21") (pintype "passive"))
    )
    (net (code "105") (name "unconnected-(JP1-Pad22)") (class "Default")
      (node (ref "JP1") (pin "22") (pinfunction "22_22") (pintype "passive"))
    )
    (net (code "106") (name "unconnected-(JP1-Pad23)") (class "Default")
      (node (ref "JP1") (pin "23") (pinfunction "23_23") (pintype "passive"))
    )
    (net (code "107") (name "unconnected-(JP1-Pad24)") (class "Default")
      (node (ref "JP1") (pin "24") (pinfunction "24_24") (pintype "passive"))
    )
    (net (code "108") (name "unconnected-(JP1-Pad25)") (class "Default")
      (node (ref "JP1") (pin "25") (pinfunction "25_25") (pintype "passive"))
    )
    (net (code "109") (name "unconnected-(JP1-Pad26)") (class "Default")
      (node (ref "JP1") (pin "26") (pinfunction "26_26") (pintype "passive"))
    )
    (net (code "110") (name "unconnected-(JP1-Pad27)") (class "Default")
      (node (ref "JP1") (pin "27") (pinfunction "27_27") (pintype "passive"))
    )
    (net (code "111") (name "unconnected-(JP1-Pad28)") (class "Default")
      (node (ref "JP1") (pin "28") (pinfunction "28_28") (pintype "passive"))
    )
    (net (code "112") (name "unconnected-(JP1-Pad29)") (class "Default")
      (node (ref "JP1") (pin "29") (pinfunction "29_29") (pintype "passive"))
    )
    (net (code "113") (name "unconnected-(JP1-Pad30)") (class "Default")
      (node (ref "JP1") (pin "30") (pinfunction "30_30") (pintype "passive"))
    )
    (net (code "114") (name "unconnected-(JP1-Pad31)") (class "Default")
      (node (ref "JP1") (pin "31") (pinfunction "31_31") (pintype "passive"))
    )
    (net (code "115") (name "unconnected-(JP1-Pad32)") (class "Default")
      (node (ref "JP1") (pin "32") (pinfunction "32_32") (pintype "passive"))
    )
    (net (code "116") (name "unconnected-(JP1-Pad33)") (class "Default")
      (node (ref "JP1") (pin "33") (pinfunction "33_33") (pintype "passive"))
    )
    (net (code "117") (name "unconnected-(JP1-Pad34)") (class "Default")
      (node (ref "JP1") (pin "34") (pinfunction "34_34") (pintype "passive"))
    )
    (net (code "118") (name "unconnected-(JP1-Pad35)") (class "Default")
      (node (ref "JP1") (pin "35") (pinfunction "35_35") (pintype "passive"))
    )
    (net (code "119") (name "unconnected-(JP1-Pad36)") (class "Default")
      (node (ref "JP1") (pin "36") (pinfunction "36_36") (pintype "passive"))
    )
    (net (code "120") (name "unconnected-(JP1-Pad37)") (class "Default")
      (node (ref "JP1") (pin "37") (pinfunction "37_37") (pintype "passive"))
    )
    (net (code "121") (name "unconnected-(JP1-Pad38)") (class "Default")
      (node (ref "JP1") (pin "38") (pinfunction "38_38") (pintype "passive"))
    )
    (net (code "122") (name "unconnected-(JP1-Pad39)") (class "Default")
      (node (ref "JP1") (pin "39") (pinfunction "39_39") (pintype "passive"))
    )
    (net (code "123") (name "unconnected-(JP1-Pad40)") (class "Default")
      (node (ref "JP1") (pin "40") (pinfunction "40_40") (pintype "passive"))
    )
    (net (code "124") (name "unconnected-(R1-Pad1)") (class "Default")
      (node (ref "R1") (pin "1") (pinfunction "1_1") (pintype "passive"))
    )
    (net (code "125") (name "unconnected-(R1-Pad2)") (class "Default")
      (node (ref "R1") (pin "2") (pinfunction "2_2") (pintype "passive"))
    )
    (net (code "126") (name "unconnected-(X1-KEY-Pad4)") (class "Default")
      (node (ref "X1") (pin "4") (pinfunction "KEY_4") (pintype "bidirectional"))
    )
    (net (code "127") (name "unconnected-(X5-Pad1)") (class "Default")
      (node (ref "X5") (pin "1") (pinfunction "1_1") (pintype "passive"))
    )
    (net (code "128") (name "unconnected-(X5-Pad2)") (class "Default")
      (node (ref "X5") (pin "2") (pinfunction "2_2") (pintype "passive"))
    )
    (net (code "129") (name "unconnected-(X5-Pad3)") (class "Default")
      (node (ref "X5") (pin "3") (pinfunction "3_3") (pintype "passive"))
    )
    (net (code "130") (name "unconnected-(X5-Pad4)") (class "Default")
      (node (ref "X5") (pin "4") (pinfunction "4_4") (pintype "passive"))
    )
    (net (code "131") (name "unconnected-(X5-Pad5)") (class "Default")
      (node (ref "X5") (pin "5") (pinfunction "5_5") (pintype "passive"))
    )
    (net (code "132") (name "unconnected-(X5-Pad6)") (class "Default")
      (node (ref "X5") (pin "6") (pinfunction "6_6") (pintype "passive"))
    )
    (net (code "133") (name "unconnected-(X5-Pad7)") (class "Default")
      (node (ref "X5") (pin "7") (pinfunction "7_7") (pintype "passive"))
    )
    (net (code "134") (name "unconnected-(X5-Pad8)") (class "Default")
      (node (ref "X5") (pin "8") (pinfunction "8_8") (pintype "passive"))
    )
    (net (code "135") (name "unconnected-(X5-Pad9)") (class "Default")
      (node (ref "X5") (pin "9") (pinfunction "9_9") (pintype "passive"))
    )
    (net (code "136") (name "unconnected-(X5-Pad10)") (class "Default")
      (node (ref "X5") (pin "10") (pinfunction "10_10") (pintype "passive"))
    )
    (net (code "137") (name "unconnected-(X5-Pad11)") (class "Default")
      (node (ref "X5") (pin "11") (pinfunction "11_11") (pintype "passive"))
    )
    (net (code "138") (name "unconnected-(X5-Pad12)") (class "Default")
      (node (ref "X5") (pin "12") (pinfunction "12_12") (pintype "passive"))
    )
    (net (code "139") (name "unconnected-(X5-Pad13)") (class "Default")
      (node (ref "X5") (pin "13") (pinfunction "13_13") (pintype "passive"))
    )
    (net (code "140") (name "unconnected-(X5-Pad14)") (class "Default")
      (node (ref "X5") (pin "14") (pinfunction "14_14") (pintype "passive"))
    )
    (net (code "141") (name "unconnected-(X5-Pad15)") (class "Default")
      (node (ref "X5") (pin "15") (pinfunction "15_15") (pintype "passive"))
    )
    (net (code "142") (name "unconnected-(X5-Pad16)") (class "Default")
      (node (ref "X5") (pin "16") (pinfunction "16_16") (pintype "passive"))
    )
    (net (code "143") (name "unconnected-(X5-Pad17)") (class "Default")
      (node (ref "X5") (pin "17") (pinfunction "17_17") (pintype "passive"))
    )
    (net (code "144") (name "unconnected-(X5-Pad18)") (class "Default")
      (node (ref "X5") (pin "18") (pinfunction "18_18") (pintype "passive"))
    )
    (net (code "145") (name "unconnected-(X5-Pad19)") (class "Default")
      (node (ref "X5") (pin "19") (pinfunction "19_19") (pintype "passive"))
    )
    (net (code "146") (name "unconnected-(X5-Pad20)") (class "Default")
      (node (ref "X5") (pin "20") (pinfunction "20_20") (pintype "passive"))
    )
    (net (code "147") (name "unconnected-(X5-Pad21)") (class "Default")
      (node (ref "X5") (pin "21") (pinfunction "21_21") (pintype "passive"))
    )
    (net (code "148") (name "unconnected-(X5-Pad22)") (class "Default")
      (node (ref "X5") (pin "22") (pinfunction "22_22") (pintype "passive"))
    )
    (net (code "149") (name "unconnected-(X5-Pad23)") (class "Default")
      (node (ref "X5") (pin "23") (pinfunction "23_23") (pintype "passive"))
    )
    (net (code "150") (name "unconnected-(X5-Pad24)") (class "Default")
      (node (ref "X5") (pin "24") (pinfunction "24_24") (pintype "passive"))
    )
    (net (code "151") (name "unconnected-(X5-Pad25)") (class "Default")
      (node (ref "X5") (pin "25") (pinfunction "25_25") (pintype "passive"))
    )
  )
)
